# remote.net
KiCad netlist of a schematic drawn in EAGLE
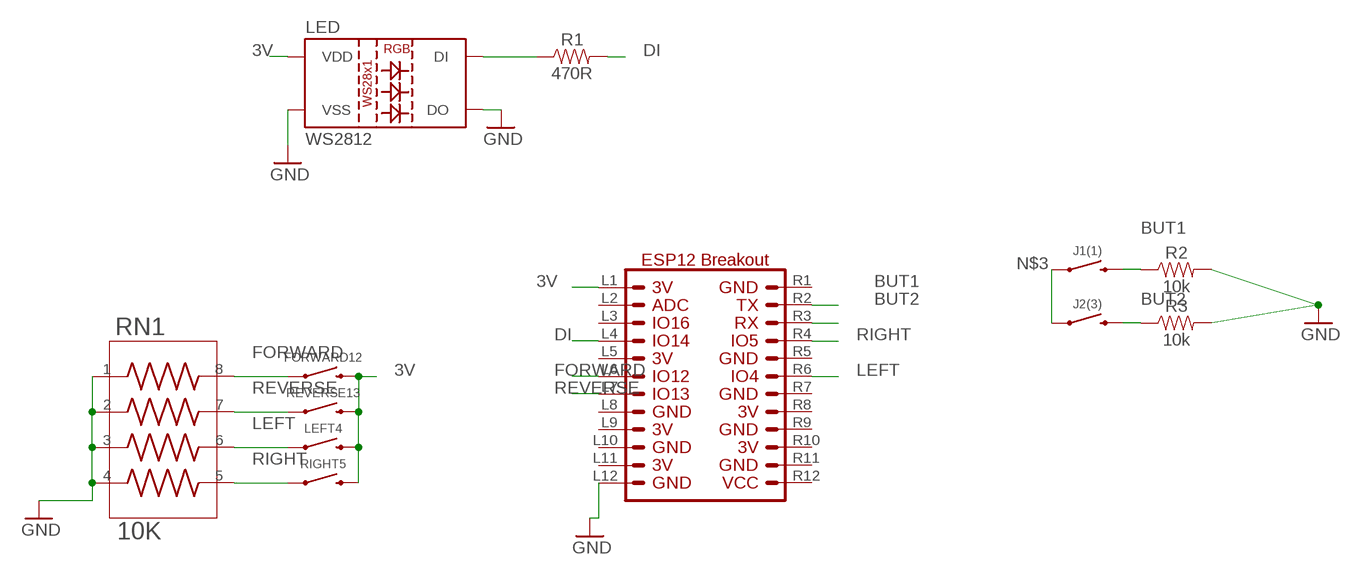
[diagram p0: schematic, sheet 1]

(export (version "E")
  (design (tool "Eeschema 10.0.6"))
  (components
    (comp (ref "FORWARD12")
      (value "PUSHBUTTON_THD")
      (footprint "eagle-import:TACTILE_SWITCH_PTH_6.0MM")
      (libsource (lib "eagle-import") (part "PUSHBUTTON_THD"))
    )
    (comp (ref "J1(1)")
      (value "PUSHBUTTON_THD")
      (footprint "eagle-import:TACTILE_SWITCH_PTH_6.0MM")
      (libsource (lib "eagle-import") (part "PUSHBUTTON_THD"))
    )
    (comp (ref "J2(3)")
      (value "PUSHBUTTON_THD")
      (footprint "eagle-import:TACTILE_SWITCH_PTH_6.0MM")
      (libsource (lib "eagle-import") (part "PUSHBUTTON_THD"))
    )
    (comp (ref "LED")
      (value "WS2812")
      (footprint "eagle-import:LED-TRICOLOR-5050-IC")
      (libsource (lib "eagle-import") (part "WS2812"))
    )
    (comp (ref "LEFT4")
      (value "PUSHBUTTON_THD")
      (footprint "eagle-import:TACTILE_SWITCH_PTH_6.0MM")
      (libsource (lib "eagle-import") (part "PUSHBUTTON_THD"))
    )
    (comp (ref "R1")
      (value "470R")
      (footprint "eagle-import:SPARKFUN-RESISTORS_1206")
      (libsource (lib "eagle-import") (part "RESISTOR_1206"))
    )
    (comp (ref "R2")
      (value "10k")
      (footprint "eagle-import:SPARKFUN-RESISTORS_1206")
      (libsource (lib "eagle-import") (part "RESISTOR_1206"))
    )
    (comp (ref "R3")
      (value "10k")
      (footprint "eagle-import:SPARKFUN-RESISTORS_1206")
      (libsource (lib "eagle-import") (part "RESISTOR_1206"))
    )
    (comp (ref "REVERSE13")
      (value "PUSHBUTTON_THD")
      (footprint "eagle-import:TACTILE_SWITCH_PTH_6.0MM")
      (libsource (lib "eagle-import") (part "PUSHBUTTON_THD"))
    )
    (comp (ref "RIGHT5")
      (value "PUSHBUTTON_THD")
      (footprint "eagle-import:TACTILE_SWITCH_PTH_6.0MM")
      (libsource (lib "eagle-import") (part "PUSHBUTTON_THD"))
    )
    (comp (ref "RN1")
      (value "10K")
      (footprint "eagle-import:RESCAF80P320X160X60-8N")
      (fields (field (name "MF") "Bourns") (field (name "MP") "CAY16-750J4LF"))
      (libsource (lib "eagle-import") (part "RESISTOR_ARRAY_1206"))
    )
    (comp (ref "U$1")
      (value "ESP12_BREAKOUT")
      (footprint "eagle-import:ESP12_BREAKOUT_CONN")
      (libsource (lib "eagle-import") (part "ESP12_BREAKOUT"))
    )
  )
  (nets
    (net (code "1") (name "/3V") (class "Default")
      (node (ref "FORWARD12") (pin "3") (pinfunction "2_3") (pintype "passive"))
      (node (ref "LED") (pin "VDD") (pinfunction "VDD_VDD") (pintype "bidirectional"))
      (node (ref "LEFT4") (pin "3") (pinfunction "2_3") (pintype "passive"))
      (node (ref "REVERSE13") (pin "3") (pinfunction "2_3") (pintype "passive"))
      (node (ref "RIGHT5") (pin "3") (pinfunction "2_3") (pintype "passive"))
      (node (ref "U$1") (pin "L1") (pinfunction "L1_L1") (pintype "passive"))
    )
    (net (code "2") (name "/BUT1") (class "Default")
      (node (ref "J1(1)") (pin "3") (pinfunction "2_3") (pintype "passive"))
      (node (ref "R2") (pin "1") (pinfunction "1_1") (pintype "passive"))
      (node (ref "U$1") (pin "R2") (pinfunction "R2_R2") (pintype "passive"))
    )
    (net (code "3") (name "/BUT2") (class "Default")
      (node (ref "J2(3)") (pin "3") (pinfunction "2_3") (pintype "passive"))
      (node (ref "R3") (pin "1") (pinfunction "1_1") (pintype "passive"))
      (node (ref "U$1") (pin "R3") (pinfunction "R3_R3") (pintype "passive"))
    )
    (net (code "4") (name "/DI") (class "Default")
      (node (ref "R1") (pin "2") (pinfunction "2_2") (pintype "passive"))
      (node (ref "U$1") (pin "L4") (pinfunction "L4_L4") (pintype "passive"))
    )
    (net (code "5") (name "/FORWARD") (class "Default")
      (node (ref "FORWARD12") (pin "1") (pinfunction "1_1") (pintype "passive"))
      (node (ref "RN1") (pin "8") (pinfunction "8_8") (pintype "passive"))
      (node (ref "U$1") (pin "L6") (pinfunction "L6_L6") (pintype "passive"))
    )
    (net (code "6") (name "/LEFT") (class "Default")
      (node (ref "LEFT4") (pin "1") (pinfunction "1_1") (pintype "passive"))
      (node (ref "RN1") (pin "6") (pinfunction "6_6") (pintype "passive"))
      (node (ref "U$1") (pin "R6") (pinfunction "R6_R6") (pintype "passive"))
    )
    (net (code "7") (name "/N$3") (class "Default")
      (node (ref "J1(1)") (pin "1") (pinfunction "1_1") (pintype "passive"))
      (node (ref "J2(3)") (pin "1") (pinfunction "1_1") (pintype "passive"))
    )
    (net (code "8") (name "/REVERSE") (class "Default")
      (node (ref "REVERSE13") (pin "1") (pinfunction "1_1") (pintype "passive"))
      (node (ref "RN1") (pin "7") (pinfunction "7_7") (pintype "passive"))
      (node (ref "U$1") (pin "L7") (pinfunction "L7_L7") (pintype "passive"))
    )
    (net (code "9") (name "/RIGHT") (class "Default")
      (node (ref "RIGHT5") (pin "1") (pinfunction "1_1") (pintype "passive"))
      (node (ref "RN1") (pin "5") (pinfunction "5_5") (pintype "passive"))
      (node (ref "U$1") (pin "R4") (pinfunction "R4_R4") (pintype "passive"))
    )
    (net (code "10") (name "GND") (class "Default")
      (node (ref "LED") (pin "DOUT") (pinfunction "DO_DOUT") (pintype "bidirectional"))
      (node (ref "LED") (pin "VSS") (pinfunction "VSS_VSS") (pintype "bidirectional"))
      (node (ref "R2") (pin "2") (pinfunction "2_2") (pintype "passive"))
      (node (ref "R3") (pin "2") (pinfunction "2_2") (pintype "passive"))
      (node (ref "RN1") (pin "1") (pinfunction "1_1") (pintype "passive"))
      (node (ref "RN1") (pin "2") (pinfunction "2_2") (pintype "passive"))
      (node (ref "RN1") (pin "3") (pinfunction "3_3") (pintype "passive"))
      (node (ref "RN1") (pin "4") (pinfunction "4_4") (pintype "passive"))
      (node (ref "U$1") (pin "L12") (pinfunction "L12_L12") (pintype "passive"))
    )
    (net (code "11") (name "Net-(LED-DI)") (class "Default")
      (node (ref "LED") (pin "DIN") (pinfunction "DI_DIN") (pintype "bidirectional"))
      (node (ref "R1") (pin "1") (pinfunction "1_1") (pintype "passive"))
    )
    (net (code "12") (name "unconnected-(U$1-PadL2)") (class "Default")
      (node (ref "U$1") (pin "L2") (pinfunction "L2_L2") (pintype "passive"))
    )
    (net (code "13") (name "unconnected-(U$1-PadL3)") (class "Default")
      (node (ref "U$1") (pin "L3") (pinfunction "L3_L3") (pintype "passive"))
    )
    (net (code "14") (name "unconnected-(U$1-PadL5)") (class "Default")
      (node (ref "U$1") (pin "L5") (pinfunction "L5_L5") (pintype "passive"))
    )
    (net (code "15") (name "unconnected-(U$1-PadL8)") (class "Default")
      (node (ref "U$1") (pin "L8") (pinfunction "L8_L8") (pintype "passive"))
    )
    (net (code "16") (name "unconnected-(U$1-PadL9)") (class "Default")
      (node (ref "U$1") (pin "L9") (pinfunction "L9_L9") (pintype "passive"))
    )
    (net (code "17") (name "unconnected-(U$1-PadL10)") (class "Default")
      (node (ref "U$1") (pin "L10") (pinfunction "L10_L10") (pintype "passive"))
    )
    (net (code "18") (name "unconnected-(U$1-PadL11)") (class "Default")
      (node (ref "U$1") (pin "L11") (pinfunction "L11_L11") (pintype "passive"))
    )
    (net (code "19") (name "unconnected-(U$1-PadR1)") (class "Default")
      (node (ref "U$1") (pin "R1") (pinfunction "R1_R1") (pintype "passive"))
    )
    (net (code "20") (name "unconnected-(U$1-PadR5)") (class "Default")
      (node (ref "U$1") (pin "R5") (pinfunction "R5_R5") (pintype "passive"))
    )
    (net (code "21") (name "unconnected-(U$1-PadR7)") (class "Default")
      (node (ref "U$1") (pin "R7") (pinfunction "R7_R7") (pintype "passive"))
    )
    (net (code "22") (name "unconnected-(U$1-PadR8)") (class "Default")
      (node (ref "U$1") (pin "R8") (pinfunction "R8_R8") (pintype "passive"))
    )
    (net (code "23") (name "unconnected-(U$1-PadR9)") (class "Default")
      (node (ref "U$1") (pin "R9") (pinfunction "R9_R9") (pintype "passive"))
    )
    (net (code "24") (name "unconnected-(U$1-PadR10)") (class "Default")
      (node (ref "U$1") (pin "R10") (pinfunction "R10_R10") (pintype "passive"))
    )
    (net (code "25") (name "unconnected-(U$1-PadR11)") (class "Default")
      (node (ref "U$1") (pin "R11") (pinfunction "R11_R11") (pintype "passive"))
    )
    (net (code "26") (name "unconnected-(U$1-PadR12)") (class "Default")
      (node (ref "U$1") (pin "R12") (pinfunction "R12_R12") (pintype "passive"))
    )
  )
)
